# psu.net
KiCad netlist of a schematic drawn in EAGLE
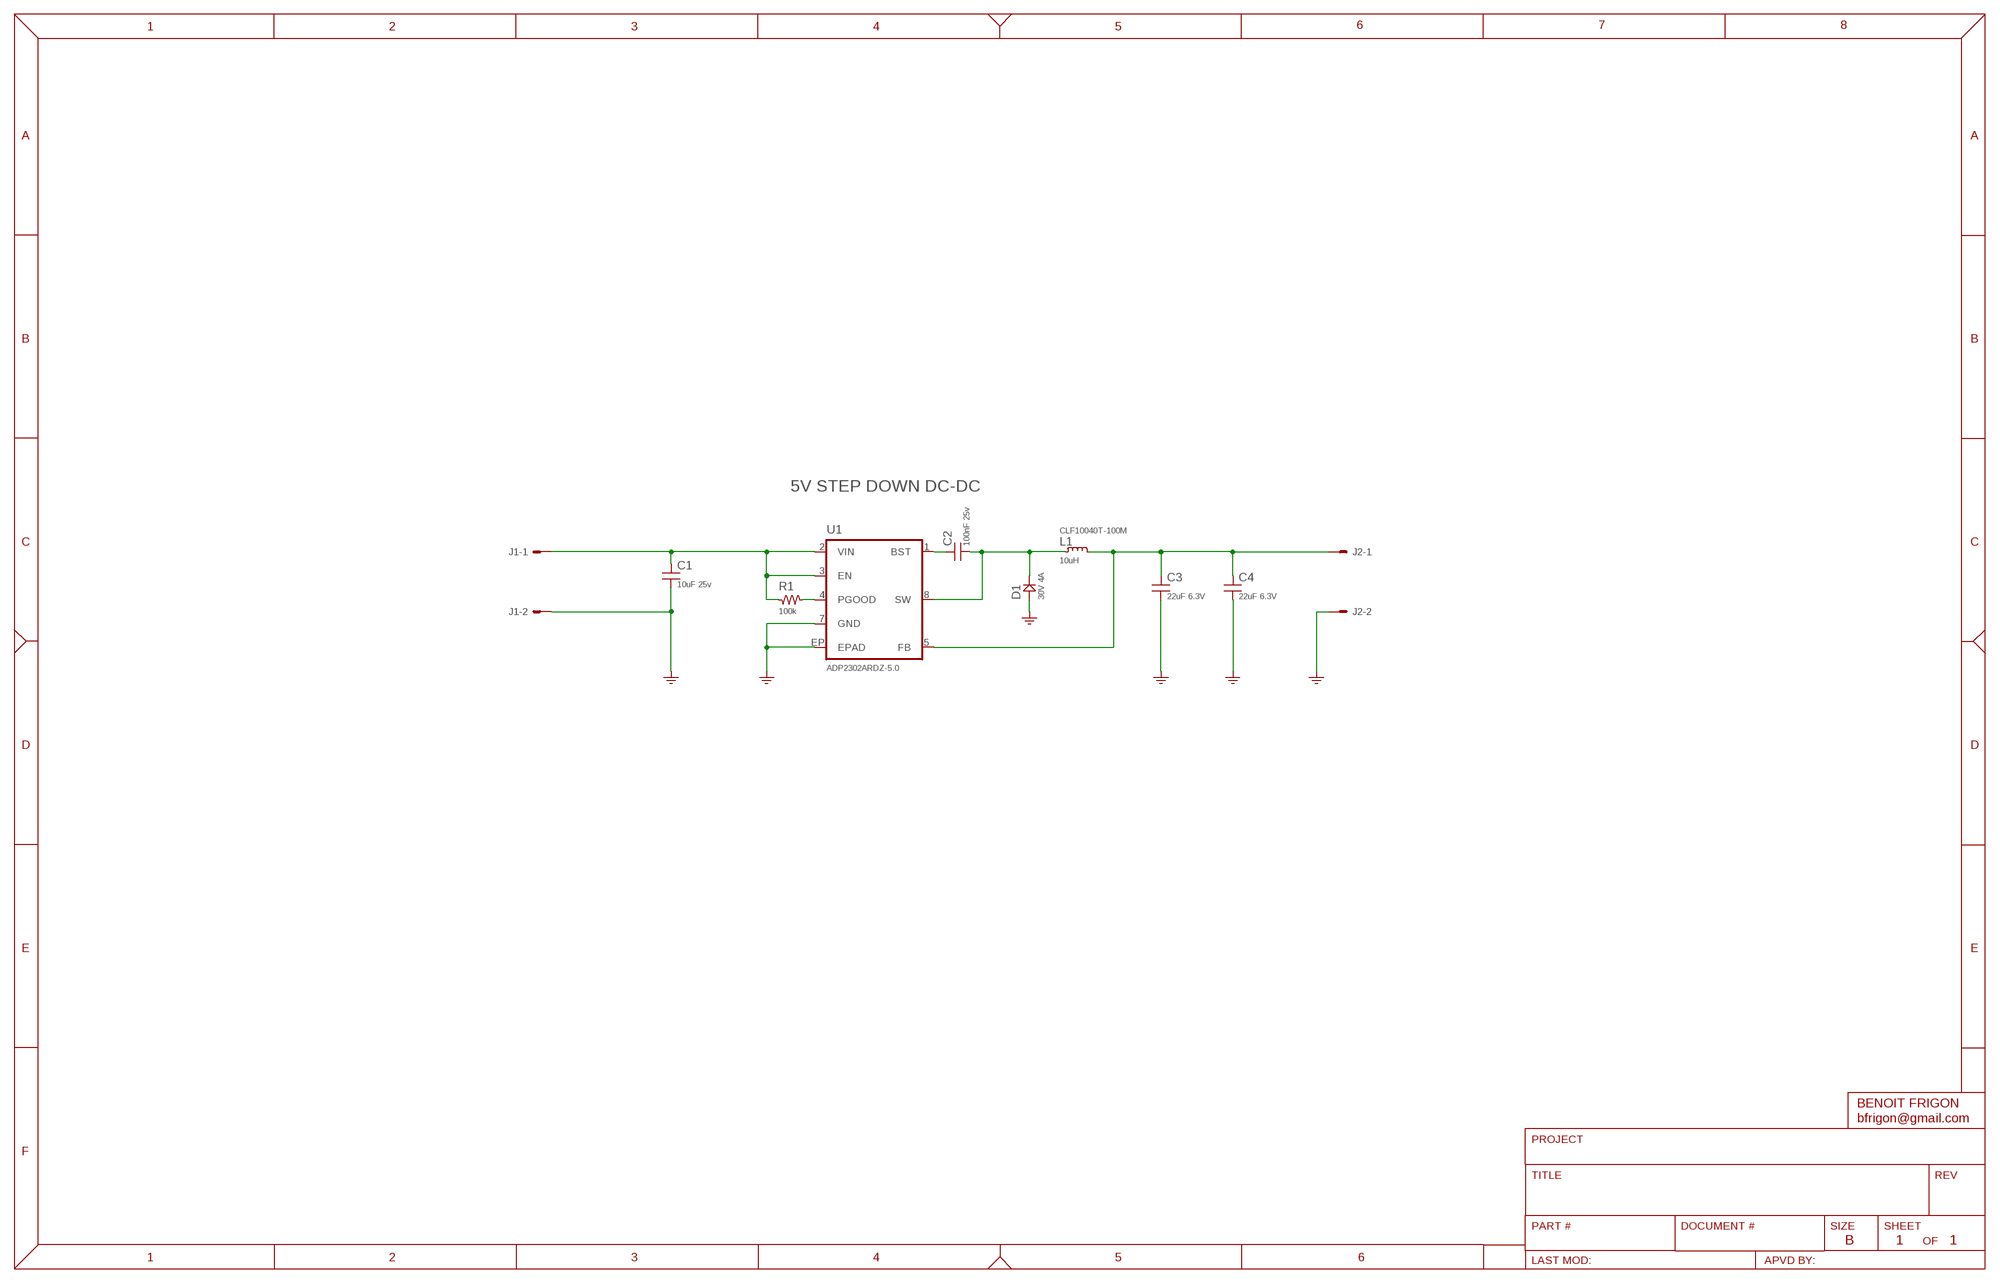
[diagram p0: schematic, sheet 1]

(export (version "E")
  (design (tool "Eeschema 10.0.6"))
  (components
    (comp (ref "C1")
      (value "10uF 25v")
      (footprint "eagle-import:SMD_1206")
      (description "{DESCRIPTION} - SMT 1206 - {value}")
      (fields (field (name "PACKAGE") "SMT 1206"))
      (libsource (lib "eagle-import") (part "CAP-1206"))
    )
    (comp (ref "C2")
      (value "100nF 25v")
      (footprint "eagle-import:SMD_0603")
      (libsource (lib "eagle-import") (part "CAP-0603"))
    )
    (comp (ref "C3")
      (value "22uF 6.3V")
      (footprint "eagle-import:SMD_1206")
      (libsource (lib "eagle-import") (part "CAP-1206"))
    )
    (comp (ref "C4")
      (value "22uF 6.3V")
      (footprint "eagle-import:SMD_1206")
      (description "{DESCRIPTION} - SMT 1206 - {value}")
      (fields (field (name "PACKAGE") "SMT 1206"))
      (libsource (lib "eagle-import") (part "CAP-1206"))
    )
    (comp (ref "D1")
      (value "30V 4A")
      (footprint "eagle-import:DIODE_DO214-AA")
      (libsource (lib "eagle-import") (part "DIODE-DO214-AA"))
    )
    (comp (ref "J1")
      (value "SNG-100-HEADER-03-HDR-V")
      (footprint "eagle-import:HDR_M_3")
      (libsource (lib "eagle-import") (part "SNG-100-HEADER-03-HDR-V"))
    )
    (comp (ref "J2")
      (value "SNG-100-HEADER-03-HDR-V")
      (footprint "eagle-import:HDR_M_3")
      (libsource (lib "eagle-import") (part "SNG-100-HEADER-03-HDR-V"))
    )
    (comp (ref "L1")
      (value "10uH")
      (footprint "eagle-import:IND-10X10")
      (fields (field (name "MFG") "TDK") (field (name "PART_NO") "CLF10040T-100M"))
      (libsource (lib "eagle-import") (part "IND?-10X10"))
    )
    (comp (ref "R1")
      (value "100k")
      (footprint "eagle-import:SMD_0603")
      (libsource (lib "eagle-import") (part "RES-0603"))
    )
    (comp (ref "U1")
      (value "ADP2302ARDZ-5.0")
      (footprint "eagle-import:SOIC8-EP")
      (description "{DESCRIPTION} - 2A, 5V")
      (fields (field (name "MFG") "Analog Devices"))
      (libsource (lib "eagle-import") (part "ADP230?2ARDZ-5.0"))
    )
  )
  (nets
    (net (code "1") (name "GND") (class "Default")
      (node (ref "C1") (pin "2") (pinfunction "2_2") (pintype "passive"))
      (node (ref "C3") (pin "2") (pinfunction "2_2") (pintype "passive"))
      (node (ref "C4") (pin "2") (pinfunction "2_2") (pintype "passive"))
      (node (ref "D1") (pin "A") (pinfunction "A_A") (pintype "passive"))
      (node (ref "J1") (pin "2") (pinfunction "S_2") (pintype "bidirectional"))
      (node (ref "J2") (pin "2") (pinfunction "S_2") (pintype "bidirectional"))
      (node (ref "U1") (pin "7") (pinfunction "GND_7") (pintype "bidirectional"))
      (node (ref "U1") (pin "EP") (pinfunction "EPAD_EP") (pintype "bidirectional"))
    )
    (net (code "2") (name "Net-(J1A-S)") (class "Default")
      (node (ref "C1") (pin "1") (pinfunction "1_1") (pintype "passive"))
      (node (ref "J1") (pin "1") (pinfunction "S_1") (pintype "bidirectional"))
      (node (ref "R1") (pin "1") (pinfunction "1_1") (pintype "passive"))
      (node (ref "U1") (pin "2") (pinfunction "VIN_2") (pintype "bidirectional"))
      (node (ref "U1") (pin "3") (pinfunction "EN_3") (pintype "bidirectional"))
    )
    (net (code "3") (name "Net-(J2A-S)") (class "Default")
      (node (ref "C3") (pin "1") (pinfunction "1_1") (pintype "passive"))
      (node (ref "C4") (pin "1") (pinfunction "1_1") (pintype "passive"))
      (node (ref "J2") (pin "1") (pinfunction "S_1") (pintype "bidirectional"))
      (node (ref "L1") (pin "2") (pinfunction "2_2") (pintype "passive"))
      (node (ref "U1") (pin "5") (pinfunction "FB_5") (pintype "bidirectional"))
    )
    (net (code "4") (name "Net-(U1-BST)") (class "Default")
      (node (ref "C2") (pin "1") (pinfunction "1_1") (pintype "passive"))
      (node (ref "U1") (pin "1") (pinfunction "BST_1") (pintype "bidirectional"))
    )
    (net (code "5") (name "Net-(U1-PGOOD)") (class "Default")
      (node (ref "R1") (pin "2") (pinfunction "2_2") (pintype "passive"))
      (node (ref "U1") (pin "4") (pinfunction "PGOOD_4") (pintype "bidirectional"))
    )
    (net (code "6") (name "Net-(U1-SW)") (class "Default")
      (node (ref "C2") (pin "2") (pinfunction "2_2") (pintype "passive"))
      (node (ref "D1") (pin "K") (pinfunction "K_K") (pintype "passive"))
      (node (ref "L1") (pin "1") (pinfunction "1_1") (pintype "passive"))
      (node (ref "U1") (pin "8") (pinfunction "SW_8") (pintype "bidirectional"))
    )
  )
)
